# Digital_Clock_SCH.net
KiCad netlist of a schematic drawn in Altium Designer
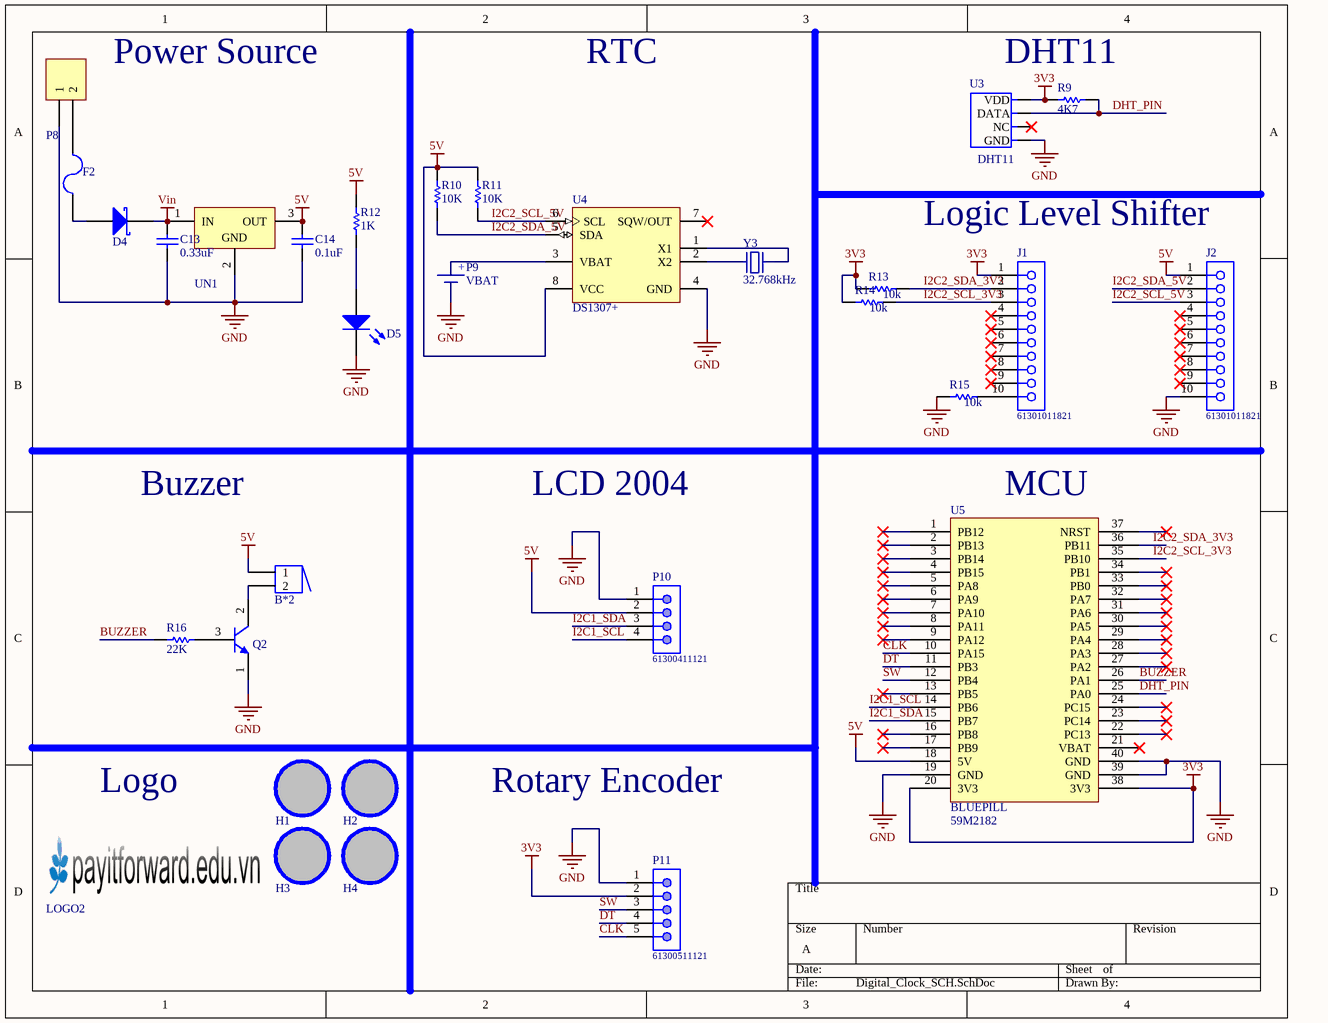
[diagram p0: Digital_Clock_SCH.SchDoc]

(export (version "E")
  (design (tool "Eeschema 10.0.6"))
  (components
    (comp (ref "B*2") (value "Buzzer") (footprint "BUZZER") (libsource (lib "PIF_Library") (part "Buzzer")))
    (comp (ref "C13")
      (value "0.33uF")
      (footprint "CAP-SM-0805")
      (description "Capacitor")
      (fields (field (name "Comment") "Cap Non-Pol SMD"))
      (libsource (lib "PIF_Library") (part "Cap Non-Pol SMD"))
    )
    (comp (ref "C14")
      (value "0.1uF")
      (footprint "CAP-SM-0805")
      (description "Capacitor")
      (fields (field (name "Comment") "Cap Non-Pol SMD"))
      (libsource (lib "PIF_Library") (part "Cap Non-Pol SMD"))
    )
    (comp (ref "D4")
      (value "D Schottky")
      (footprint "SS34")
      (description "Schottky Diode")
      (fields (field (name "PUBLISHER") "Altium Limited"))
      (libsource (lib "PIF_Library") (part "D Schottky"))
    )
    (comp (ref "D5") (value "LED") (footprint "LED-3mm") (libsource (lib "PIF_Library") (part "LED")))
    (comp (ref "F2") (value "Fuse") (footprint "FUSE SMD") (libsource (lib "PIF_Library") (part "Fuse")))
    (comp (ref "H1")
      (value "Hole")
      (footprint "LO KHOAN 3MM")
      (description "Hole 3mm")
      (libsource (lib "PIF_Library") (part "Hole"))
    )
    (comp (ref "H2")
      (value "Hole")
      (footprint "LO KHOAN 3MM")
      (description "Hole 3mm")
      (libsource (lib "PIF_Library") (part "Hole"))
    )
    (comp (ref "H3")
      (value "Hole")
      (footprint "LO KHOAN 3MM")
      (description "Hole 3mm")
      (libsource (lib "PIF_Library") (part "Hole"))
    )
    (comp (ref "H4")
      (value "Hole")
      (footprint "LO KHOAN 3MM")
      (description "Hole 3mm")
      (libsource (lib "PIF_Library") (part "Hole"))
    )
    (comp (ref "J1")
      (value "61301011821")
      (footprint "61301011821")
      (description "WR-PHD Socket Header, THT, pitch 2.54mm, Single Row, Vertical, 10p")
      (fields (field (name "MANUFACTURER") "Wurth Elektronik"))
      (libsource (lib "Altium_WR-PHD (rev20a)") (part "61301011821"))
    )
    (comp (ref "J2")
      (value "61301011821")
      (footprint "61301011821")
      (description "WR-PHD Socket Header, THT, pitch 2.54mm, Single Row, Vertical, 10p")
      (fields (field (name "MANUFACTURER") "Wurth Elektronik"))
      (libsource (lib "Altium_WR-PHD (rev20a)") (part "61301011821"))
    )
    (comp (ref "LOGO2")
      (value "LOGO PIF")
      (footprint "PIF LOGO SMALL TOP")
      (libsource (lib "PIF_Library") (part "LOGO PIF"))
    )
    (comp (ref "P8")
      (value "Domino 2")
      (footprint "DOMINO SMALL 2")
      (description "Domino, 2-Pin")
      (fields (field (name "PUBLISHER") "Altium Limited"))
      (libsource (lib "PIF_Library") (part "Domino 2"))
    )
    (comp (ref "P9")
      (value "VBAT")
      (footprint "VBAT CR2030")
      (description "CR2032")
      (fields
        (field (name "MANUFACTURER") "DANTONA INDUSTRIES")
        (field (name "MANUFACTURER PART NUMBER") "CR2032 SANYO")
      )
      (libsource (lib "DeltaCross_Libs") (part "VBAT CR2032"))
    )
    (comp (ref "P10")
      (value "61300411121")
      (footprint "61300411121")
      (description "WR-PHD Pin Header, THT, pitch 2.54mm, Single Row, Vertical, 4p")
      (fields (field (name "MANUFACTURER") "Wurth Elektronik"))
      (libsource (lib "Altium_WR-PHD (rev20a)") (part "61300411121"))
    )
    (comp (ref "P11")
      (value "61300511121")
      (footprint "61300511121")
      (description "WR-PHD Pin Header, THT, pitch 2.54mm, Single Row, Vertical, 5p")
      (fields (field (name "MANUFACTURER") "Wurth Elektronik"))
      (libsource (lib "Altium_WR-PHD (rev20a)") (part "61300511121"))
    )
    (comp (ref "Q2")
      (value "C1815")
      (footprint "QTO-92")
      (description "NPN Bipolar Transistor")
      (libsource (lib "PIF_Library") (part "C1815"))
    )
    (comp (ref "R9")
      (value "4K7")
      (footprint "RES-SM-0805")
      (description "Resistor")
      (fields (field (name "Comment") "RESISTOR SMD"))
      (libsource (lib "PIF_Library") (part "RESISTOR SMD"))
    )
    (comp (ref "R10")
      (value "10K")
      (footprint "RES-SM-0805")
      (description "Resistor")
      (fields (field (name "Comment") "RESISTOR SMD"))
      (libsource (lib "PIF_Library") (part "RESISTOR SMD"))
    )
    (comp (ref "R11")
      (value "10K")
      (footprint "RES-SM-0805")
      (description "Resistor")
      (fields (field (name "Comment") "RESISTOR SMD"))
      (libsource (lib "PIF_Library") (part "RESISTOR SMD"))
    )
    (comp (ref "R12")
      (value "1K")
      (footprint "RES-SM-0805")
      (description "Resistor")
      (fields (field (name "Comment") "RESISTOR SMD"))
      (libsource (lib "PIF_Library") (part "RESISTOR SMD"))
    )
    (comp (ref "R13")
      (value "10k")
      (footprint "RES-SM-0805")
      (description "Resistor")
      (fields (field (name "Comment") "RESISTOR SMD"))
      (libsource (lib "PIF_Library") (part "RESISTOR SMD"))
    )
    (comp (ref "R14")
      (value "10k")
      (footprint "RES-SM-0805")
      (description "Resistor")
      (fields (field (name "Comment") "RESISTOR SMD"))
      (libsource (lib "PIF_Library") (part "RESISTOR SMD"))
    )
    (comp (ref "R15")
      (value "10k")
      (footprint "RES-SM-0805")
      (description "Resistor")
      (fields (field (name "Comment") "RESISTOR SMD"))
      (libsource (lib "PIF_Library") (part "RESISTOR SMD"))
    )
    (comp (ref "R16")
      (value "22K")
      (footprint "RES-SM-0805")
      (description "Resistor")
      (fields (field (name "Comment") "RESISTOR SMD"))
      (libsource (lib "PIF_Library") (part "RESISTOR SMD"))
    )
    (comp (ref "U3")
      (value "DHT11")
      (footprint "SNR4-2.54-15.5X12.0X5.5MM")
      (description "Servo AC 100 ~ 120VAC Supply 10A 120V Load")
      (fields (field (name "MF") "Panasonic Industrial Automation Sales"))
      (libsource (lib "TEM-HUM-DHT11_4P-15.5X12.0MM_") (part "TEM-HUM-DHT11(4P-15.5X12.0MM)"))
    )
    (comp (ref "U4")
      (value "DS1307+")
      (footprint "MAXM-P8-1")
      (description "I2C Real-Time Clock, 5 V, 0 to 70 degC, 8-Pin DIP, RoHS, Tube")
      (fields (field (name "MANUFACTURER") "Maxim"))
      (libsource (lib "HCMUT") (part "MAXM-DS1307Z+-8"))
    )
    (comp (ref "U5")
      (value "BLUEPILL")
      (footprint "BLUEPILL")
      (description "Development board STM32F103C8T6")
      (fields (field (name "SUPPLIER PART NUMBER 1") "59M2182"))
      (libsource (lib "Giang's Libs") (part "BLUEPILL"))
    )
    (comp (ref "UN1")
      (value "LM7805")
      (footprint "QTO-220")
      (description "Positive Voltage Regulator")
      (libsource (lib "PIF_Library") (part "LM7805"))
    )
    (comp (ref "Y3")
      (value "32.768kHz")
      (footprint "XTAL 32768 3x8")
      (description "Crystal For all Crystal 2pin")
      (libsource (lib "DeltaCross_Libs") (part "XTAL"))
    )
  )
  (nets
    (net (code "1") (name "/BUZZER") (class "Default")
      (node (ref "R16") (pin "1") (pinfunction "1_1") (pintype "passive"))
      (node (ref "U5") (pin "26") (pinfunction "PA1_26") (pintype "passive"))
    )
    (net (code "2") (name "/CLK") (class "Default")
      (node (ref "P11") (pin "5") (pinfunction "5_5") (pintype "passive"))
      (node (ref "U5") (pin "10") (pinfunction "PA15_10") (pintype "passive"))
    )
    (net (code "3") (name "/DHT_PIN") (class "Default")
      (node (ref "R9") (pin "2") (pinfunction "2_2") (pintype "passive"))
      (node (ref "U3") (pin "2") (pinfunction "DATA_2") (pintype "bidirectional"))
      (node (ref "U5") (pin "25") (pinfunction "PA0_25") (pintype "passive"))
    )
    (net (code "4") (name "/DT") (class "Default")
      (node (ref "P11") (pin "4") (pinfunction "4_4") (pintype "passive"))
      (node (ref "U5") (pin "11") (pinfunction "PB3_11") (pintype "passive"))
    )
    (net (code "5") (name "/I2C1_SCL") (class "Default")
      (node (ref "P10") (pin "4") (pinfunction "4_4") (pintype "passive"))
      (node (ref "U5") (pin "14") (pinfunction "PB6_14") (pintype "passive"))
    )
    (net (code "6") (name "/I2C1_SDA") (class "Default")
      (node (ref "P10") (pin "3") (pinfunction "3_3") (pintype "passive"))
      (node (ref "U5") (pin "15") (pinfunction "PB7_15") (pintype "passive"))
    )
    (net (code "7") (name "/I2C2_SCL_3V3") (class "Default")
      (node (ref "J1") (pin "3") (pinfunction "3_3") (pintype "passive"))
      (node (ref "R14") (pin "2") (pinfunction "2_2") (pintype "passive"))
      (node (ref "U5") (pin "35") (pinfunction "PB10_35") (pintype "passive"))
    )
    (net (code "8") (name "/I2C2_SCL_5V") (class "Default")
      (node (ref "J2") (pin "3") (pinfunction "3_3") (pintype "passive"))
      (node (ref "R11") (pin "1") (pinfunction "1_1") (pintype "passive"))
      (node (ref "U4") (pin "6") (pinfunction "SCL_6") (pintype "input"))
    )
    (net (code "9") (name "/I2C2_SDA_3V3") (class "Default")
      (node (ref "J1") (pin "2") (pinfunction "2_2") (pintype "passive"))
      (node (ref "R13") (pin "2") (pinfunction "2_2") (pintype "passive"))
      (node (ref "U5") (pin "36") (pinfunction "PB11_36") (pintype "passive"))
    )
    (net (code "10") (name "/I2C2_SDA_5V") (class "Default")
      (node (ref "J2") (pin "2") (pinfunction "2_2") (pintype "passive"))
      (node (ref "R10") (pin "1") (pinfunction "1_1") (pintype "passive"))
      (node (ref "U4") (pin "5") (pinfunction "SDA_5") (pintype "bidirectional"))
    )
    (net (code "11") (name "/SW") (class "Default")
      (node (ref "P11") (pin "3") (pinfunction "3_3") (pintype "passive"))
      (node (ref "U5") (pin "12") (pinfunction "PB4_12") (pintype "passive"))
    )
    (net (code "12") (name "3V3") (class "Default")
      (node (ref "J1") (pin "1") (pinfunction "1_1") (pintype "passive"))
      (node (ref "P11") (pin "2") (pinfunction "2_2") (pintype "passive"))
      (node (ref "R13") (pin "1") (pinfunction "1_1") (pintype "passive"))
      (node (ref "R14") (pin "1") (pinfunction "1_1") (pintype "passive"))
      (node (ref "R9") (pin "1") (pinfunction "1_1") (pintype "passive"))
      (node (ref "U3") (pin "1") (pinfunction "VDD_1") (pintype "power_in"))
      (node (ref "U5") (pin "20") (pinfunction "3V3_20") (pintype "passive"))
      (node (ref "U5") (pin "38") (pinfunction "3V3_38") (pintype "passive"))
    )
    (net (code "13") (name "5V") (class "Default")
      (node (ref "B*2") (pin "1") (pinfunction "1_1") (pintype "passive"))
      (node (ref "C14") (pin "2") (pinfunction "2_2") (pintype "passive"))
      (node (ref "J2") (pin "1") (pinfunction "1_1") (pintype "passive"))
      (node (ref "P10") (pin "2") (pinfunction "2_2") (pintype "passive"))
      (node (ref "R10") (pin "2") (pinfunction "2_2") (pintype "passive"))
      (node (ref "R11") (pin "2") (pinfunction "2_2") (pintype "passive"))
      (node (ref "R12") (pin "1") (pinfunction "1_1") (pintype "passive"))
      (node (ref "U4") (pin "8") (pinfunction "VCC_8") (pintype "power_in"))
      (node (ref "U5") (pin "18") (pinfunction "5V_18") (pintype "passive"))
      (node (ref "UN1") (pin "3") (pinfunction "OUT_3") (pintype "power_in"))
    )
    (net (code "14") (name "GND") (class "Default")
      (node (ref "C13") (pin "1") (pinfunction "1_1") (pintype "passive"))
      (node (ref "C14") (pin "1") (pinfunction "1_1") (pintype "passive"))
      (node (ref "D5") (pin "2") (pinfunction "K_2") (pintype "passive"))
      (node (ref "J2") (pin "10") (pinfunction "10_10") (pintype "passive"))
      (node (ref "P10") (pin "1") (pinfunction "1_1") (pintype "passive"))
      (node (ref "P11") (pin "1") (pinfunction "1_1") (pintype "passive"))
      (node (ref "P8") (pin "1") (pinfunction "1_1") (pintype "passive"))
      (node (ref "P9") (pin "2") (pinfunction "+_2") (pintype "passive"))
      (node (ref "Q2") (pin "1") (pinfunction "E_1") (pintype "passive"))
      (node (ref "R15") (pin "1") (pinfunction "1_1") (pintype "passive"))
      (node (ref "U3") (pin "4") (pinfunction "GND_4") (pintype "power_in"))
      (node (ref "U4") (pin "4") (pinfunction "GND_4") (pintype "power_in"))
      (node (ref "U5") (pin "19") (pinfunction "GND_19") (pintype "passive"))
      (node (ref "U5") (pin "39") (pinfunction "GND_39") (pintype "passive"))
      (node (ref "U5") (pin "40") (pinfunction "GND_40") (pintype "passive"))
      (node (ref "UN1") (pin "2") (pinfunction "GND_2") (pintype "power_in"))
    )
    (net (code "15") (name "Net-(D4-A)") (class "Default")
      (node (ref "D4") (pin "1") (pinfunction "A_1") (pintype "passive"))
      (node (ref "F2") (pin "2") (pinfunction "2_2") (pintype "passive"))
    )
    (net (code "16") (name "Net-(D5-A)") (class "Default")
      (node (ref "D5") (pin "1") (pinfunction "A_1") (pintype "passive"))
      (node (ref "R12") (pin "2") (pinfunction "2_2") (pintype "passive"))
    )
    (net (code "17") (name "Net-(F2-Pad1)") (class "Default")
      (node (ref "F2") (pin "1") (pinfunction "1_1") (pintype "passive"))
      (node (ref "P8") (pin "2") (pinfunction "2_2") (pintype "passive"))
    )
    (net (code "18") (name "Net-(J1-Pad10)") (class "Default")
      (node (ref "J1") (pin "10") (pinfunction "10_10") (pintype "passive"))
      (node (ref "R15") (pin "2") (pinfunction "2_2") (pintype "passive"))
    )
    (net (code "19") (name "Net-(Q2-B)") (class "Default")
      (node (ref "Q2") (pin "3") (pinfunction "B_3") (pintype "passive"))
      (node (ref "R16") (pin "2") (pinfunction "2_2") (pintype "passive"))
    )
    (net (code "20") (name "Net-(Q2-C)") (class "Default")
      (node (ref "B*2") (pin "2") (pinfunction "2_2") (pintype "passive"))
      (node (ref "Q2") (pin "2") (pinfunction "C_2") (pintype "passive"))
    )
    (net (code "21") (name "Net-(U4-VBAT)") (class "Default")
      (node (ref "P9") (pin "1") (pinfunction "+_1") (pintype "passive"))
      (node (ref "U4") (pin "3") (pinfunction "VBAT_3") (pintype "power_in"))
    )
    (net (code "22") (name "Net-(U4-X1)") (class "Default")
      (node (ref "U4") (pin "1") (pinfunction "X1_1") (pintype "passive"))
      (node (ref "Y3") (pin "2") (pinfunction "2_2") (pintype "passive"))
    )
    (net (code "23") (name "Net-(U4-X2)") (class "Default")
      (node (ref "U4") (pin "2") (pinfunction "X2_2") (pintype "passive"))
      (node (ref "Y3") (pin "1") (pinfunction "1_1") (pintype "passive"))
    )
    (net (code "24") (name "Vin") (class "Default")
      (node (ref "C13") (pin "2") (pinfunction "2_2") (pintype "passive"))
      (node (ref "D4") (pin "2") (pinfunction "K_2") (pintype "passive"))
      (node (ref "UN1") (pin "1") (pinfunction "IN_1") (pintype "power_in"))
    )
    (net (code "25") (name "unconnected-(H1-Pad1)") (class "Default")
      (node (ref "H1") (pin "1") (pinfunction "1_1") (pintype "passive"))
    )
    (net (code "26") (name "unconnected-(H2-Pad1)") (class "Default")
      (node (ref "H2") (pin "1") (pinfunction "1_1") (pintype "passive"))
    )
    (net (code "27") (name "unconnected-(H3-Pad1)") (class "Default")
      (node (ref "H3") (pin "1") (pinfunction "1_1") (pintype "passive"))
    )
    (net (code "28") (name "unconnected-(H4-Pad1)") (class "Default")
      (node (ref "H4") (pin "1") (pinfunction "1_1") (pintype "passive"))
    )
    (net (code "29") (name "unconnected-(J1-Pad4)") (class "Default")
      (node (ref "J1") (pin "4") (pinfunction "4_4") (pintype "passive+no_connect"))
    )
    (net (code "30") (name "unconnected-(J1-Pad5)") (class "Default")
      (node (ref "J1") (pin "5") (pinfunction "5_5") (pintype "passive+no_connect"))
    )
    (net (code "31") (name "unconnected-(J1-Pad6)") (class "Default")
      (node (ref "J1") (pin "6") (pinfunction "6_6") (pintype "passive+no_connect"))
    )
    (net (code "32") (name "unconnected-(J1-Pad7)") (class "Default")
      (node (ref "J1") (pin "7") (pinfunction "7_7") (pintype "passive+no_connect"))
    )
    (net (code "33") (name "unconnected-(J1-Pad8)") (class "Default")
      (node (ref "J1") (pin "8") (pinfunction "8_8") (pintype "passive+no_connect"))
    )
    (net (code "34") (name "unconnected-(J1-Pad9)") (class "Default")
      (node (ref "J1") (pin "9") (pinfunction "9_9") (pintype "passive+no_connect"))
    )
    (net (code "35") (name "unconnected-(J2-Pad4)") (class "Default")
      (node (ref "J2") (pin "4") (pinfunction "4_4") (pintype "passive+no_connect"))
    )
    (net (code "36") (name "unconnected-(J2-Pad5)") (class "Default")
      (node (ref "J2") (pin "5") (pinfunction "5_5") (pintype "passive+no_connect"))
    )
    (net (code "37") (name "unconnected-(J2-Pad6)") (class "Default")
      (node (ref "J2") (pin "6") (pinfunction "6_6") (pintype "passive+no_connect"))
    )
    (net (code "38") (name "unconnected-(J2-Pad7)") (class "Default")
      (node (ref "J2") (pin "7") (pinfunction "7_7") (pintype "passive+no_connect"))
    )
    (net (code "39") (name "unconnected-(J2-Pad8)") (class "Default")
      (node (ref "J2") (pin "8") (pinfunction "8_8") (pintype "passive+no_connect"))
    )
    (net (code "40") (name "unconnected-(J2-Pad9)") (class "Default")
      (node (ref "J2") (pin "9") (pinfunction "9_9") (pintype "passive+no_connect"))
    )
    (net (code "41") (name "unconnected-(U3-NC-Pad3)") (class "Default")
      (node (ref "U3") (pin "3") (pinfunction "NC_3") (pintype "passive+no_connect"))
    )
    (net (code "42") (name "unconnected-(U4-SQW{slash}OUT-Pad7)") (class "Default")
      (node (ref "U4") (pin "7") (pinfunction "SQW/OUT_7") (pintype "open_collector+no_connect"))
    )
    (net (code "43") (name "unconnected-(U5-NRST-Pad37)") (class "Default")
      (node (ref "U5") (pin "37") (pinfunction "NRST_37") (pintype "passive+no_connect"))
    )
    (net (code "44") (name "unconnected-(U5-PA2-Pad27)") (class "Default")
      (node (ref "U5") (pin "27") (pinfunction "PA2_27") (pintype "passive+no_connect"))
    )
    (net (code "45") (name "unconnected-(U5-PA3-Pad28)") (class "Default")
      (node (ref "U5") (pin "28") (pinfunction "PA3_28") (pintype "passive+no_connect"))
    )
    (net (code "46") (name "unconnected-(U5-PA4-Pad29)") (class "Default")
      (node (ref "U5") (pin "29") (pinfunction "PA4_29") (pintype "passive+no_connect"))
    )
    (net (code "47") (name "unconnected-(U5-PA5-Pad30)") (class "Default")
      (node (ref "U5") (pin "30") (pinfunction "PA5_30") (pintype "passive+no_connect"))
    )
    (net (code "48") (name "unconnected-(U5-PA6-Pad31)") (class "Default")
      (node (ref "U5") (pin "31") (pinfunction "PA6_31") (pintype "passive+no_connect"))
    )
    (net (code "49") (name "unconnected-(U5-PA7-Pad32)") (class "Default")
      (node (ref "U5") (pin "32") (pinfunction "PA7_32") (pintype "passive+no_connect"))
    )
    (net (code "50") (name "unconnected-(U5-PA8-Pad5)") (class "Default")
      (node (ref "U5") (pin "5") (pinfunction "PA8_5") (pintype "passive+no_connect"))
    )
    (net (code "51") (name "unconnected-(U5-PA9-Pad6)") (class "Default")
      (node (ref "U5") (pin "6") (pinfunction "PA9_6") (pintype "passive+no_connect"))
    )
    (net (code "52") (name "unconnected-(U5-PA10-Pad7)") (class "Default")
      (node (ref "U5") (pin "7") (pinfunction "PA10_7") (pintype "passive+no_connect"))
    )
    (net (code "53") (name "unconnected-(U5-PA11-Pad8)") (class "Default")
      (node (ref "U5") (pin "8") (pinfunction "PA11_8") (pintype "passive+no_connect"))
    )
    (net (code "54") (name "unconnected-(U5-PA12-Pad9)") (class "Default")
      (node (ref "U5") (pin "9") (pinfunction "PA12_9") (pintype "passive+no_connect"))
    )
    (net (code "55") (name "unconnected-(U5-PB0-Pad33)") (class "Default")
      (node (ref "U5") (pin "33") (pinfunction "PB0_33") (pintype "passive+no_connect"))
    )
    (net (code "56") (name "unconnected-(U5-PB1-Pad34)") (class "Default")
      (node (ref "U5") (pin "34") (pinfunction "PB1_34") (pintype "passive+no_connect"))
    )
    (net (code "57") (name "unconnected-(U5-PB5-Pad13)") (class "Default")
      (node (ref "U5") (pin "13") (pinfunction "PB5_13") (pintype "passive+no_connect"))
    )
    (net (code "58") (name "unconnected-(U5-PB8-Pad16)") (class "Default")
      (node (ref "U5") (pin "16") (pinfunction "PB8_16") (pintype "passive+no_connect"))
    )
    (net (code "59") (name "unconnected-(U5-PB9-Pad17)") (class "Default")
      (node (ref "U5") (pin "17") (pinfunction "PB9_17") (pintype "passive+no_connect"))
    )
    (net (code "60") (name "unconnected-(U5-PB12-Pad1)") (class "Default")
      (node (ref "U5") (pin "1") (pinfunction "PB12_1") (pintype "passive+no_connect"))
    )
    (net (code "61") (name "unconnected-(U5-PB13-Pad2)") (class "Default")
      (node (ref "U5") (pin "2") (pinfunction "PB13_2") (pintype "passive+no_connect"))
    )
    (net (code "62") (name "unconnected-(U5-PB14-Pad3)") (class "Default")
      (node (ref "U5") (pin "3") (pinfunction "PB14_3") (pintype "passive+no_connect"))
    )
    (net (code "63") (name "unconnected-(U5-PB15-Pad4)") (class "Default")
      (node (ref "U5") (pin "4") (pinfunction "PB15_4") (pintype "passive+no_connect"))
    )
    (net (code "64") (name "unconnected-(U5-PC13-Pad22)") (class "Default")
      (node (ref "U5") (pin "22") (pinfunction "PC13_22") (pintype "passive+no_connect"))
    )
    (net (code "65") (name "unconnected-(U5-PC14-Pad23)") (class "Default")
      (node (ref "U5") (pin "23") (pinfunction "PC14_23") (pintype "passive+no_connect"))
    )
    (net (code "66") (name "unconnected-(U5-PC15-Pad24)") (class "Default")
      (node (ref "U5") (pin "24") (pinfunction "PC15_24") (pintype "passive+no_connect"))
    )
    (net (code "67") (name "unconnected-(U5-VBAT-Pad21)") (class "Default")
      (node (ref "U5") (pin "21") (pinfunction "VBAT_21") (pintype "passive+no_connect"))
    )
  )
)
